# p8_wch_link.net
KiCad netlist of a schematic drawn in Altium Designer
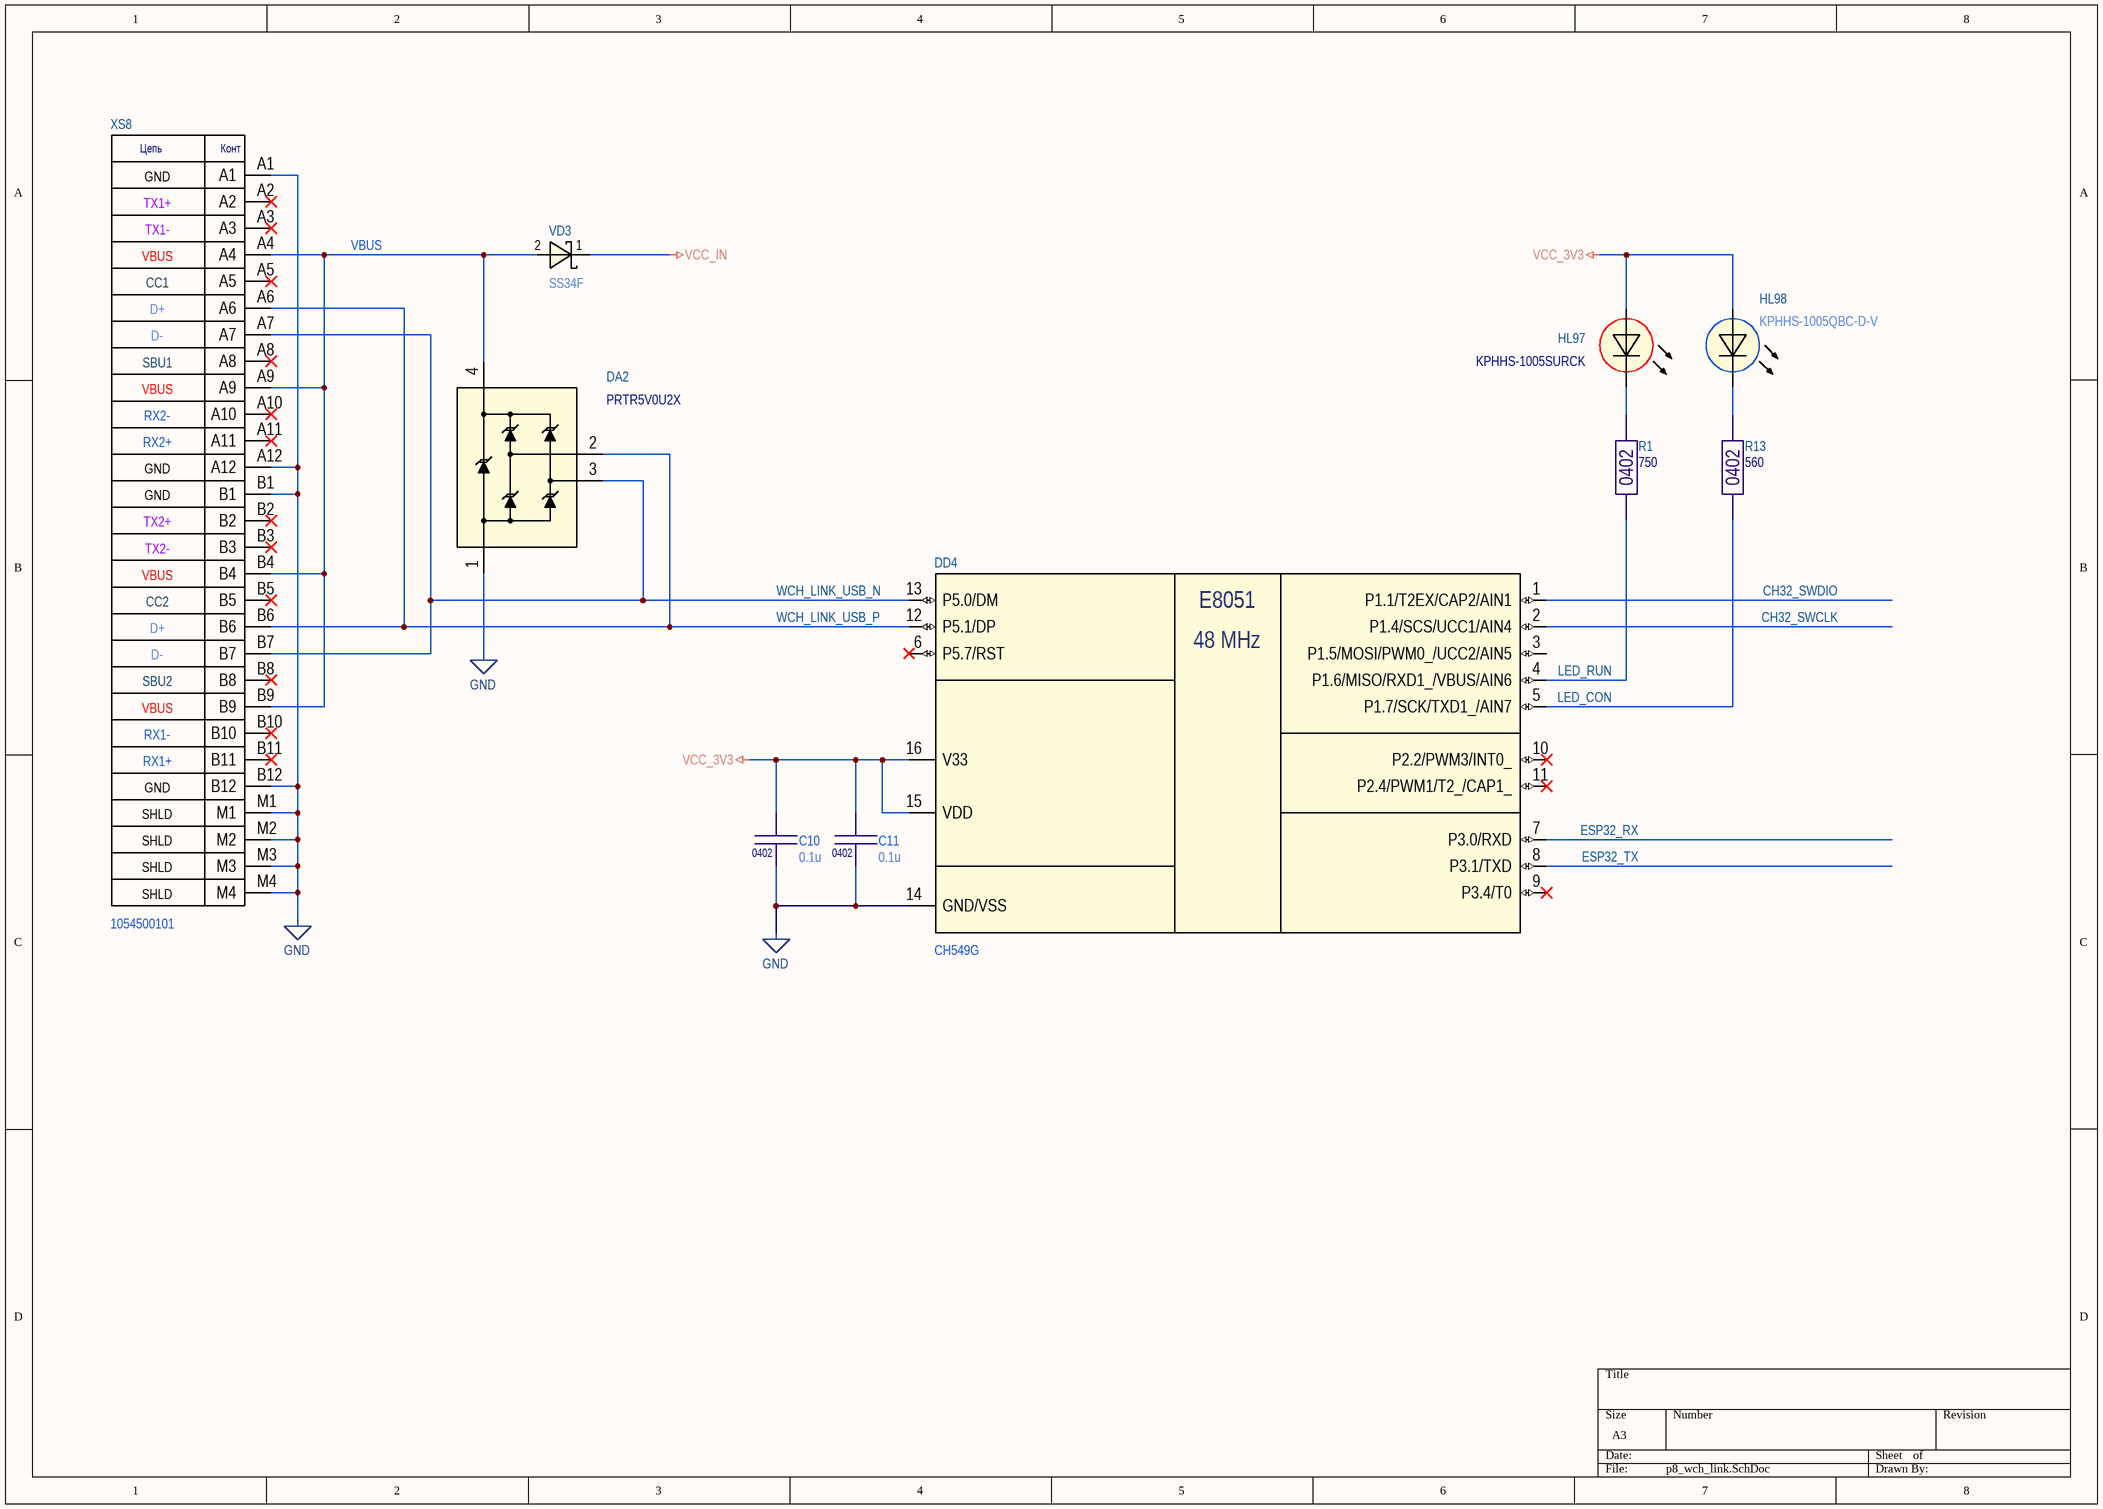
[diagram p0: p8_wch_link.SchDoc]

(export (version "E")
  (design (tool "Eeschema 10.0.6"))
  (components
    (comp (ref "C10")
      (value "0.1u")
      (footprint "PcbLib_RC:CAP0402")
      (description "Capacitors 0402 package case")
      (fields
        (field (name "TOLERANCE") "± 5 %")
        (field (name "VOLTAGE") "50 V")
        (field (name "PACKAGE") "0402")
      )
      (libsource (lib "Schlib_RC") (part "C0402"))
    )
    (comp (ref "C11")
      (value "0.1u")
      (footprint "PcbLib_RC:CAP0402")
      (description "Capacitors 0402 package case")
      (fields
        (field (name "TOLERANCE") "± 5 %")
        (field (name "VOLTAGE") "50 V")
        (field (name "PACKAGE") "0402")
      )
      (libsource (lib "Schlib_RC") (part "C0402"))
    )
    (comp (ref "DA2")
      (value "PRTR5V0U2X")
      (footprint "PcbLib_ICs:SOT143")
      (description "Ultra low capacitance double rail-to-rail ESD protection diode")
      (fields (field (name "MANUFACTURER") "NXP USA Inc."))
      (libsource (lib "Schlib_NXP_Semiconductors") (part "PRTR5V0U2X"))
    )
    (comp (ref "DD4")
      (value "CH549G")
      (footprint "PcbLib_ICs:SOIC-16")
      (description "8-bit Enhanced USB MCU")
      (fields (field (name "MANUFACTURER") "WinChipHead"))
      (libsource (lib "Schlib_WCH") (part "CH549G"))
    )
    (comp (ref "HL97")
      (value "KPHHS-1005SURCK")
      (footprint "PcbLib_Others:LED0402R")
      (description "Red led (package case 0402)")
      (fields (field (name "MANUFACTURER") "Kingbright Company LLC."))
      (libsource (lib "Schlib_Kingbright") (part "KPHHS-1005SURCK"))
    )
    (comp (ref "HL98")
      (value "KPHHS-1005QBC-D-V")
      (footprint "PcbLib_Others:LED0402B")
      (description "Blue led (package case 0402)")
      (fields (field (name "MANUFACTURER") "Kingbright Company LLC."))
      (libsource (lib "Schlib_Kingbright") (part "KPHHS-1005QBC-D-V"))
    )
    (comp (ref "R1")
      (value "750")
      (footprint "PcbLib_RC:RES0402B")
      (description "Resistor 0402 package case")
      (fields
        (field (name "TOLERANCE") "± 1 %")
        (field (name "PART NUMBER") "RC0402FR-07750RL")
        (field (name "PACKAGE") "0402")
      )
      (libsource (lib "Schlib_RC") (part "R0402"))
    )
    (comp (ref "R13")
      (value "560")
      (footprint "PcbLib_RC:RES0402B")
      (description "Resistor 0402 package case")
      (fields
        (field (name "TOLERANCE") "± 1 %")
        (field (name "PART NUMBER") "RC0402FR-07560RL")
        (field (name "PACKAGE") "0402")
      )
      (libsource (lib "Schlib_RC") (part "R0402"))
    )
    (comp (ref "VD3")
      (value "SS34F")
      (footprint "PcbLib_Discrete:SMA-FL")
      (description "3A Schottky barrier rectifier")
      (fields (field (name "MANUFACTURER") "UMW"))
      (libsource (lib "Schlib_UMW") (part "SS34F"))
    )
    (comp (ref "XS8")
      (value "1054500101")
      (footprint "PcbLib_Connectors:1054500101")
      (description "USB Shielded I/O Receptacle, Type C, Right-Angle, Top Mount, Surface Mount")
      (fields (field (name "MANUFACTURER") "Molex") (field (name "AUTHOR") "Sklyarov"))
      (libsource (lib "Schlib_MolexConnectors") (part "1054500101"))
    )
  )
  (nets
    (net (code "1") (name "/CH32_SWCLK") (class "Default")
      (node (ref "DD4") (pin "2") (pinfunction "P1.4/SCS/UCC1/AIN4_2") (pintype "bidirectional"))
    )
    (net (code "2") (name "/CH32_SWDIO") (class "Default")
      (node (ref "DD4") (pin "1") (pinfunction "P1.1/T2EX/CAP2/AIN1_1") (pintype "bidirectional"))
    )
    (net (code "3") (name "/ESP32_RX") (class "Default")
      (node (ref "DD4") (pin "7") (pinfunction "P3.0/RXD_7") (pintype "bidirectional"))
    )
    (net (code "4") (name "/ESP32_TX") (class "Default")
      (node (ref "DD4") (pin "8") (pinfunction "P3.1/TXD_8") (pintype "bidirectional"))
    )
    (net (code "5") (name "/LED_CON") (class "Default")
      (node (ref "DD4") (pin "5") (pinfunction "P1.7/SCK/TXD1_/AIN7_5") (pintype "bidirectional"))
      (node (ref "R13") (pin "2") (pinfunction "2_2") (pintype "passive"))
    )
    (net (code "6") (name "/LED_RUN") (class "Default")
      (node (ref "DD4") (pin "4") (pinfunction "P1.6/MISO/RXD1_/VBUS/AIN6_4") (pintype "bidirectional"))
      (node (ref "R1") (pin "2") (pinfunction "2_2") (pintype "passive"))
    )
    (net (code "7") (name "/VBUS") (class "Default")
      (node (ref "DA2") (pin "4") (pinfunction "VCC_4") (pintype "passive"))
      (node (ref "VD3") (pin "2") (pinfunction "2_2") (pintype "passive"))
      (node (ref "XS8") (pin "A4") (pinfunction "A4_A4") (pintype "passive"))
      (node (ref "XS8") (pin "A9") (pinfunction "A9_A9") (pintype "passive"))
      (node (ref "XS8") (pin "B4") (pinfunction "B4_B4") (pintype "passive"))
      (node (ref "XS8") (pin "B9") (pinfunction "B9_B9") (pintype "passive"))
    )
    (net (code "8") (name "/WCH_LINK_USB_N") (class "Default")
      (node (ref "DA2") (pin "3") (pinfunction "IO2_3") (pintype "passive"))
      (node (ref "DD4") (pin "13") (pinfunction "P5.0/DM_13") (pintype "bidirectional"))
      (node (ref "XS8") (pin "A7") (pinfunction "A7_A7") (pintype "passive"))
      (node (ref "XS8") (pin "B7") (pinfunction "B7_B7") (pintype "passive"))
    )
    (net (code "9") (name "/WCH_LINK_USB_P") (class "Default")
      (node (ref "DA2") (pin "2") (pinfunction "IO1_2") (pintype "passive"))
      (node (ref "DD4") (pin "12") (pinfunction "P5.1/DP_12") (pintype "bidirectional"))
      (node (ref "XS8") (pin "A6") (pinfunction "A6_A6") (pintype "passive"))
      (node (ref "XS8") (pin "B6") (pinfunction "B6_B6") (pintype "passive"))
    )
    (net (code "10") (name "GND") (class "Default")
      (node (ref "C10") (pin "2") (pinfunction "2_2") (pintype "passive"))
      (node (ref "C11") (pin "2") (pinfunction "2_2") (pintype "passive"))
      (node (ref "DA2") (pin "1") (pinfunction "GND_1") (pintype "passive"))
      (node (ref "DD4") (pin "14") (pinfunction "GND/VSS_14") (pintype "power_in"))
      (node (ref "XS8") (pin "A1") (pinfunction "A1_A1") (pintype "passive"))
      (node (ref "XS8") (pin "A12") (pinfunction "A12_A12") (pintype "passive"))
      (node (ref "XS8") (pin "B1") (pinfunction "B1_B1") (pintype "passive"))
      (node (ref "XS8") (pin "B12") (pinfunction "B12_B12") (pintype "passive"))
      (node (ref "XS8") (pin "M1") (pinfunction "M1_M1") (pintype "passive"))
      (node (ref "XS8") (pin "M2") (pinfunction "M2_M2") (pintype "passive"))
      (node (ref "XS8") (pin "M3") (pinfunction "M3_M3") (pintype "passive"))
      (node (ref "XS8") (pin "M4") (pinfunction "M4_M4") (pintype "passive"))
    )
    (net (code "11") (name "Net-(HL97-Pad1)") (class "Default")
      (node (ref "HL97") (pin "1") (pinfunction "1_1") (pintype "passive"))
      (node (ref "R1") (pin "1") (pinfunction "1_1") (pintype "passive"))
    )
    (net (code "12") (name "Net-(HL98-Pad1)") (class "Default")
      (node (ref "HL98") (pin "1") (pinfunction "1_1") (pintype "passive"))
      (node (ref "R13") (pin "1") (pinfunction "1_1") (pintype "passive"))
    )
    (net (code "13") (name "VCC_3V3") (class "Default")
      (node (ref "C10") (pin "1") (pinfunction "1_1") (pintype "passive"))
      (node (ref "C11") (pin "1") (pinfunction "1_1") (pintype "passive"))
      (node (ref "DD4") (pin "15") (pinfunction "VDD_15") (pintype "power_in"))
      (node (ref "DD4") (pin "16") (pinfunction "V33_16") (pintype "power_in"))
      (node (ref "HL97") (pin "2") (pinfunction "2_2") (pintype "passive"))
      (node (ref "HL98") (pin "2") (pinfunction "2_2") (pintype "passive"))
    )
    (net (code "14") (name "VCC_IN") (class "Default")
      (node (ref "VD3") (pin "1") (pinfunction "1_1") (pintype "passive"))
    )
    (net (code "15") (name "unconnected-(DD4-P1.5{slash}MOSI{slash}PWM0_{slash}UCC2{slash}AIN5-Pad3)") (class "Default")
      (node (ref "DD4") (pin "3") (pinfunction "P1.5/MOSI/PWM0_/UCC2/AIN5_3") (pintype "bidirectional"))
    )
    (net (code "16") (name "unconnected-(DD4-P2.2{slash}PWM3{slash}INT0_-Pad10)") (class "Default")
      (node (ref "DD4") (pin "10") (pinfunction "P2.2/PWM3/INT0__10") (pintype "bidirectional+no_connect"))
    )
    (net (code "17") (name "unconnected-(DD4-P2.4{slash}PWM1{slash}T2_{slash}CAP1_-Pad11)") (class "Default")
      (node (ref "DD4") (pin "11") (pinfunction "P2.4/PWM1/T2_/CAP1__11") (pintype "bidirectional+no_connect"))
    )
    (net (code "18") (name "unconnected-(DD4-P3.4{slash}T0-Pad9)") (class "Default")
      (node (ref "DD4") (pin "9") (pinfunction "P3.4/T0_9") (pintype "bidirectional+no_connect"))
    )
    (net (code "19") (name "unconnected-(DD4-P5.7{slash}RST-Pad6)") (class "Default")
      (node (ref "DD4") (pin "6") (pinfunction "P5.7/RST_6") (pintype "bidirectional+no_connect"))
    )
    (net (code "20") (name "unconnected-(XS8-PadA2)") (class "Default")
      (node (ref "XS8") (pin "A2") (pinfunction "A2_A2") (pintype "passive+no_connect"))
    )
    (net (code "21") (name "unconnected-(XS8-PadA3)") (class "Default")
      (node (ref "XS8") (pin "A3") (pinfunction "A3_A3") (pintype "passive+no_connect"))
    )
    (net (code "22") (name "unconnected-(XS8-PadA5)") (class "Default")
      (node (ref "XS8") (pin "A5") (pinfunction "A5_A5") (pintype "passive+no_connect"))
    )
    (net (code "23") (name "unconnected-(XS8-PadA8)") (class "Default")
      (node (ref "XS8") (pin "A8") (pinfunction "A8_A8") (pintype "passive+no_connect"))
    )
    (net (code "24") (name "unconnected-(XS8-PadA10)") (class "Default")
      (node (ref "XS8") (pin "A10") (pinfunction "A10_A10") (pintype "passive+no_connect"))
    )
    (net (code "25") (name "unconnected-(XS8-PadA11)") (class "Default")
      (node (ref "XS8") (pin "A11") (pinfunction "A11_A11") (pintype "passive+no_connect"))
    )
    (net (code "26") (name "unconnected-(XS8-PadB2)") (class "Default")
      (node (ref "XS8") (pin "B2") (pinfunction "B2_B2") (pintype "passive+no_connect"))
    )
    (net (code "27") (name "unconnected-(XS8-PadB3)") (class "Default")
      (node (ref "XS8") (pin "B3") (pinfunction "B3_B3") (pintype "passive+no_connect"))
    )
    (net (code "28") (name "unconnected-(XS8-PadB5)") (class "Default")
      (node (ref "XS8") (pin "B5") (pinfunction "B5_B5") (pintype "passive+no_connect"))
    )
    (net (code "29") (name "unconnected-(XS8-PadB8)") (class "Default")
      (node (ref "XS8") (pin "B8") (pinfunction "B8_B8") (pintype "passive+no_connect"))
    )
    (net (code "30") (name "unconnected-(XS8-PadB10)") (class "Default")
      (node (ref "XS8") (pin "B10") (pinfunction "B10_B10") (pintype "passive+no_connect"))
    )
    (net (code "31") (name "unconnected-(XS8-PadB11)") (class "Default")
      (node (ref "XS8") (pin "B11") (pinfunction "B11_B11") (pintype "passive+no_connect"))
    )
  )
)
